# power.net
KiCad netlist of a schematic drawn in EAGLE
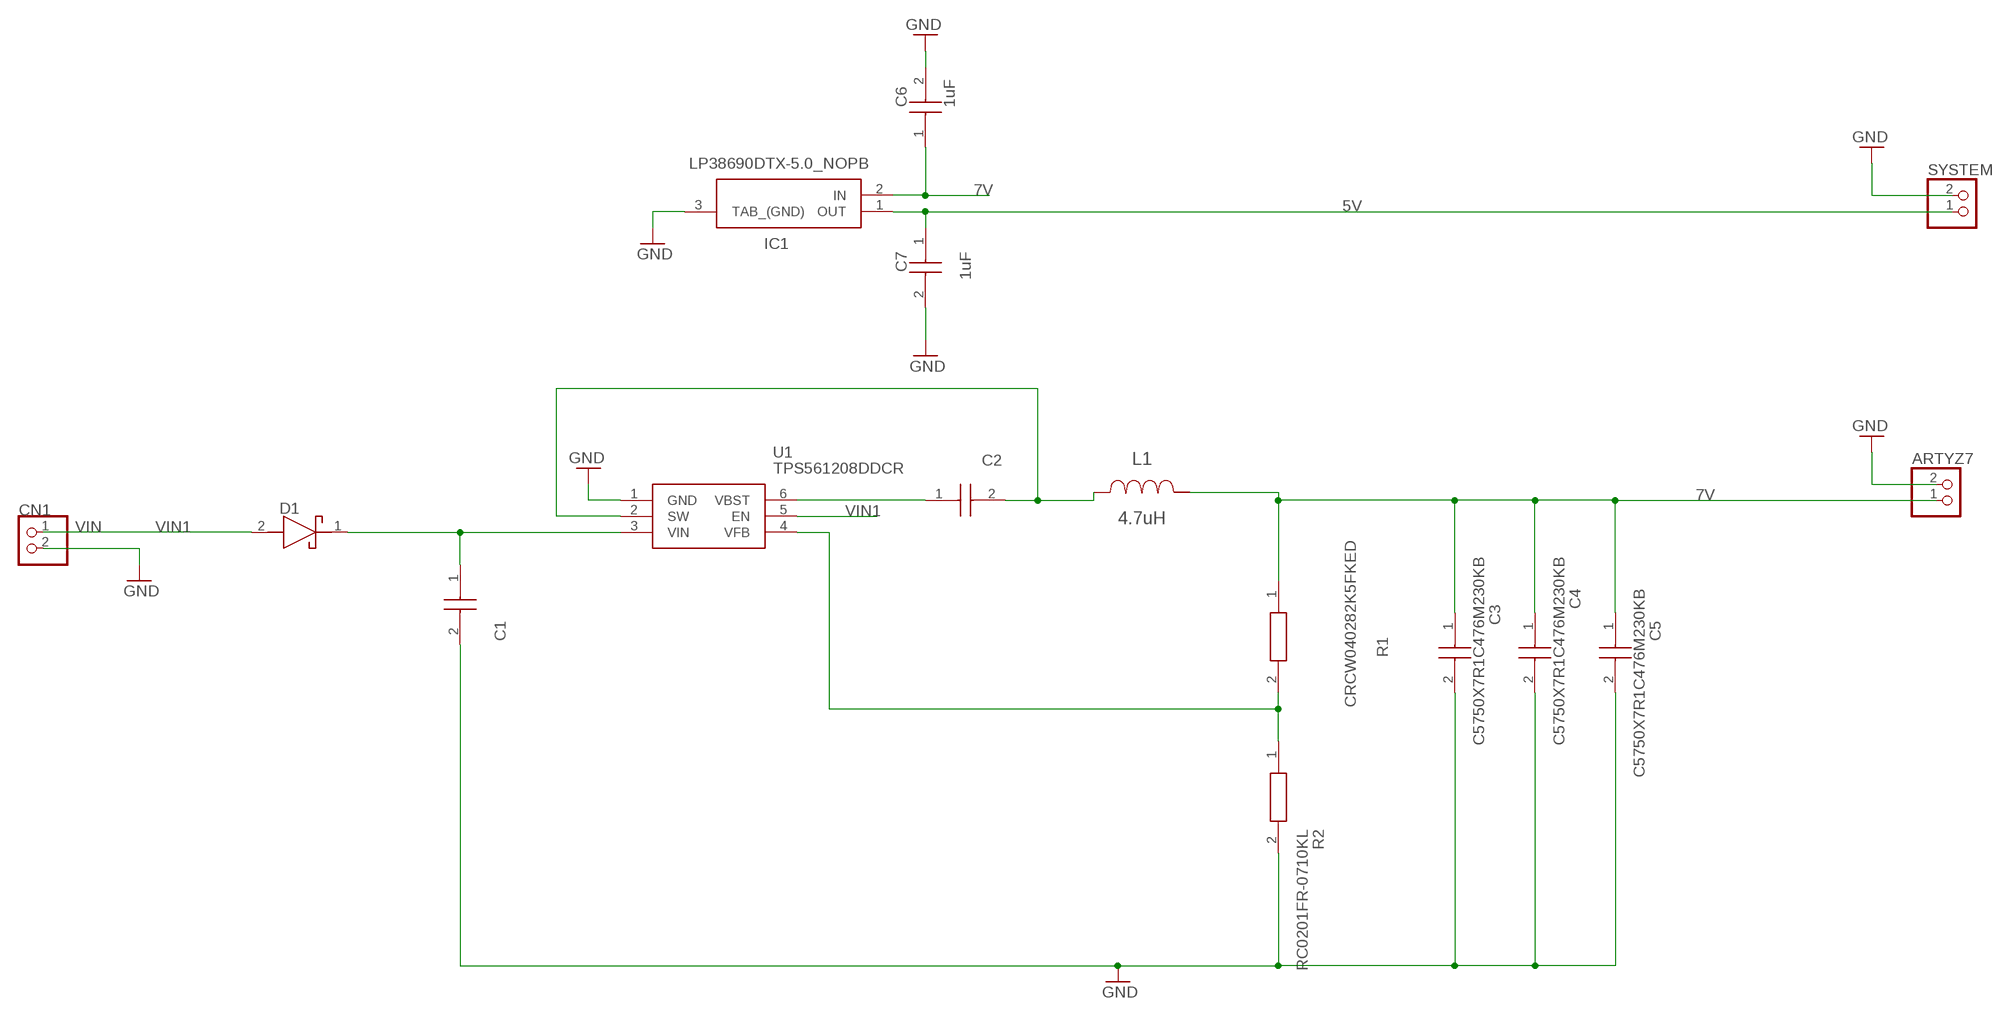
[diagram p0: schematic, sheet 1]

(export (version "E")
  (design (tool "Eeschema 10.0.6"))
  (components
    (comp (ref "ARTYZ7")
      (value "JST_2PIN-SMT-RA")
      (footprint "eagle-import:JST-PH-2-SMT-RA")
      (libsource (lib "eagle-import") (part "JST_2PIN-SMT-RA"))
    )
    (comp (ref "C1")
      (value "593D226X9025D2TE3")
      (footprint "eagle-import:CAPPM7343X310N")
      (fields (field (name "MOUSER_PART_NUMBER") "74-593D226X9025D2TE3"))
      (libsource (lib "eagle-import") (part "593D226X9025D2TE3"))
    )
    (comp (ref "C2")
      (value "C0603C104Z3VACTU")
      (footprint "eagle-import:CAPC1608X90N")
      (fields (field (name "MOUSER_PART_NUMBER") "80-C0603C104Z3V"))
      (libsource (lib "eagle-import") (part "C0603C104Z3VACTU"))
    )
    (comp (ref "C3")
      (value "C5750X7R1C476M230KB")
      (footprint "eagle-import:CAPC5750X250N")
      (fields (field (name "MOUSER_PART_NUMBER") "810-C5750X7R1C476M"))
      (libsource (lib "eagle-import") (part "C5750X7R1C476M230KB"))
    )
    (comp (ref "C4")
      (value "C5750X7R1C476M230KB")
      (footprint "eagle-import:CAPC5750X250N")
      (fields (field (name "MOUSER_PART_NUMBER") "810-C5750X7R1C476M"))
      (libsource (lib "eagle-import") (part "C5750X7R1C476M230KB"))
    )
    (comp (ref "C5")
      (value "C5750X7R1C476M230KB")
      (footprint "eagle-import:CAPC5750X250N")
      (fields (field (name "MOUSER_PART_NUMBER") "810-C5750X7R1C476M"))
      (libsource (lib "eagle-import") (part "C5750X7R1C476M230KB"))
    )
    (comp (ref "C6")
      (value "1uF")
      (footprint "eagle-import:CAPC1608X80N")
      (fields
        (field (name "MANUFACTURER_PART_NUMBER") "C1608X5R1A106M080AC")
        (field (name "MOUSER_PART_NUMBER") "810-C1608X5R1A106M")
      )
      (libsource (lib "eagle-import") (part "C1608X5R1A106M080AC"))
    )
    (comp (ref "C7")
      (value "1uF")
      (footprint "eagle-import:CAPC1608X80N")
      (fields
        (field (name "MANUFACTURER_PART_NUMBER") "C1608X5R1A106M080AC")
        (field (name "MOUSER_PART_NUMBER") "810-C1608X5R1A106M")
      )
      (libsource (lib "eagle-import") (part "C1608X5R1A106M080AC"))
    )
    (comp (ref "CN1")
      (value "JST_2PIN-SMT-RA")
      (footprint "eagle-import:JST-PH-2-SMT-RA")
      (libsource (lib "eagle-import") (part "JST_2PIN-SMT-RA"))
    )
    (comp (ref "D1")
      (value "NRVB120VLSFT1G")
      (footprint "eagle-import:SODFL3616X98N")
      (fields (field (name "MOUSER_PART_NUMBER") "863-NRVB120VLSFT1G"))
      (libsource (lib "eagle-import") (part "NRVB120VLSFT1G"))
    )
    (comp (ref "IC1")
      (value "LP38690DTX-5.0_NOPB")
      (footprint "eagle-import:LM78M05CDT")
      (fields
        (field (name "MANUFACTURER_PART_NUMBER") "LP38690DTX-5.0/NOPB")
        (field (name "MOUSER_PART_NUMBER") "926-LP38690DTX50NOPB")
      )
      (libsource (lib "eagle-import") (part "LP38690DTX-5.0_NOPB"))
    )
    (comp (ref "L1")
      (value "4.7uH")
      (footprint "eagle-import:SLF7045")
      (fields (field (name "MANUFACTURER_PART_NUMBER") "SLF7045T-4R7M2R0-PF"))
      (libsource (lib "eagle-import") (part "SLF7045T-4R7M2R0-PFSLF7045T-4R7M2R0-PF"))
    )
    (comp (ref "R1")
      (value "CRCW040282K5FKED")
      (footprint "eagle-import:RESC1005X40N")
      (fields (field (name "MOUSER_PART_NUMBER") "71-CRCW0402-82.5K-E3"))
      (libsource (lib "eagle-import") (part "CRCW040282K5FKED"))
    )
    (comp (ref "R2")
      (value "RC0201FR-0710KL")
      (footprint "eagle-import:RESC0603X26N")
      (fields (field (name "MOUSER_PART_NUMBER") "603-RC0201FR-0710KL"))
      (libsource (lib "eagle-import") (part "RC0201FR-0710KL"))
    )
    (comp (ref "SYSTEM")
      (value "JST_2PIN-SMT-RA")
      (footprint "eagle-import:JST-PH-2-SMT-RA")
      (libsource (lib "eagle-import") (part "JST_2PIN-SMT-RA"))
    )
    (comp (ref "U1")
      (value "TPS561208DDCR")
      (footprint "eagle-import:SOT95P280X110-6N")
      (fields (field (name "MOUSER_PART_NUMBER") "595-TPS561208DDCR"))
      (libsource (lib "eagle-import") (part "TPS561208DDCR"))
    )
  )
  (nets
    (net (code "1") (name "/5V") (class "Default")
      (node (ref "C7") (pin "1") (pinfunction "1_1") (pintype "bidirectional"))
      (node (ref "IC1") (pin "1") (pinfunction "OUT_1") (pintype "bidirectional"))
      (node (ref "SYSTEM") (pin "1") (pinfunction "2_1") (pintype "passive"))
    )
    (net (code "2") (name "/7V") (class "Default")
      (node (ref "ARTYZ7") (pin "1") (pinfunction "2_1") (pintype "passive"))
      (node (ref "C3") (pin "1") (pinfunction "1_1") (pintype "bidirectional"))
      (node (ref "C4") (pin "1") (pinfunction "1_1") (pintype "bidirectional"))
      (node (ref "C5") (pin "1") (pinfunction "1_1") (pintype "bidirectional"))
      (node (ref "C6") (pin "1") (pinfunction "1_1") (pintype "bidirectional"))
      (node (ref "IC1") (pin "2") (pinfunction "IN_2") (pintype "bidirectional"))
      (node (ref "L1") (pin "2") (pinfunction "2_2") (pintype "passive"))
      (node (ref "R1") (pin "1") (pinfunction "1_1") (pintype "bidirectional"))
    )
    (net (code "3") (name "/VIN") (class "Default")
      (node (ref "CN1") (pin "1") (pinfunction "2_1") (pintype "passive"))
      (node (ref "D1") (pin "2") (pinfunction "A_2") (pintype "bidirectional"))
    )
    (net (code "4") (name "/VIN1") (class "Default")
      (node (ref "C1") (pin "1") (pinfunction "+_1") (pintype "bidirectional"))
      (node (ref "D1") (pin "1") (pinfunction "K_1") (pintype "bidirectional"))
      (node (ref "U1") (pin "3") (pinfunction "VIN_3") (pintype "bidirectional"))
      (node (ref "U1") (pin "5") (pinfunction "EN_5") (pintype "bidirectional"))
    )
    (net (code "5") (name "GND") (class "Default")
      (node (ref "ARTYZ7") (pin "2") (pinfunction "1_2") (pintype "passive"))
      (node (ref "C1") (pin "2") (pinfunction "-_2") (pintype "bidirectional"))
      (node (ref "C3") (pin "2") (pinfunction "2_2") (pintype "bidirectional"))
      (node (ref "C4") (pin "2") (pinfunction "2_2") (pintype "bidirectional"))
      (node (ref "C5") (pin "2") (pinfunction "2_2") (pintype "bidirectional"))
      (node (ref "C6") (pin "2") (pinfunction "2_2") (pintype "bidirectional"))
      (node (ref "C7") (pin "2") (pinfunction "2_2") (pintype "bidirectional"))
      (node (ref "CN1") (pin "2") (pinfunction "1_2") (pintype "passive"))
      (node (ref "IC1") (pin "3") (pinfunction "TAB_(GND)_3") (pintype "bidirectional"))
      (node (ref "R2") (pin "2") (pinfunction "2_2") (pintype "bidirectional"))
      (node (ref "SYSTEM") (pin "2") (pinfunction "1_2") (pintype "passive"))
      (node (ref "U1") (pin "1") (pinfunction "GND_1") (pintype "bidirectional"))
    )
    (net (code "6") (name "Net-(U1-SW)") (class "Default")
      (node (ref "C2") (pin "2") (pinfunction "2_2") (pintype "bidirectional"))
      (node (ref "L1") (pin "1") (pinfunction "1_1") (pintype "passive"))
      (node (ref "U1") (pin "2") (pinfunction "SW_2") (pintype "bidirectional"))
    )
    (net (code "7") (name "Net-(U1-VBST)") (class "Default")
      (node (ref "C2") (pin "1") (pinfunction "1_1") (pintype "bidirectional"))
      (node (ref "U1") (pin "6") (pinfunction "VBST_6") (pintype "bidirectional"))
    )
    (net (code "8") (name "Net-(U1-VFB)") (class "Default")
      (node (ref "R1") (pin "2") (pinfunction "2_2") (pintype "bidirectional"))
      (node (ref "R2") (pin "1") (pinfunction "1_1") (pintype "bidirectional"))
      (node (ref "U1") (pin "4") (pinfunction "VFB_4") (pintype "bidirectional"))
    )
  )
)
